# Lily.net
KiCad netlist of a schematic drawn in Altium Designer
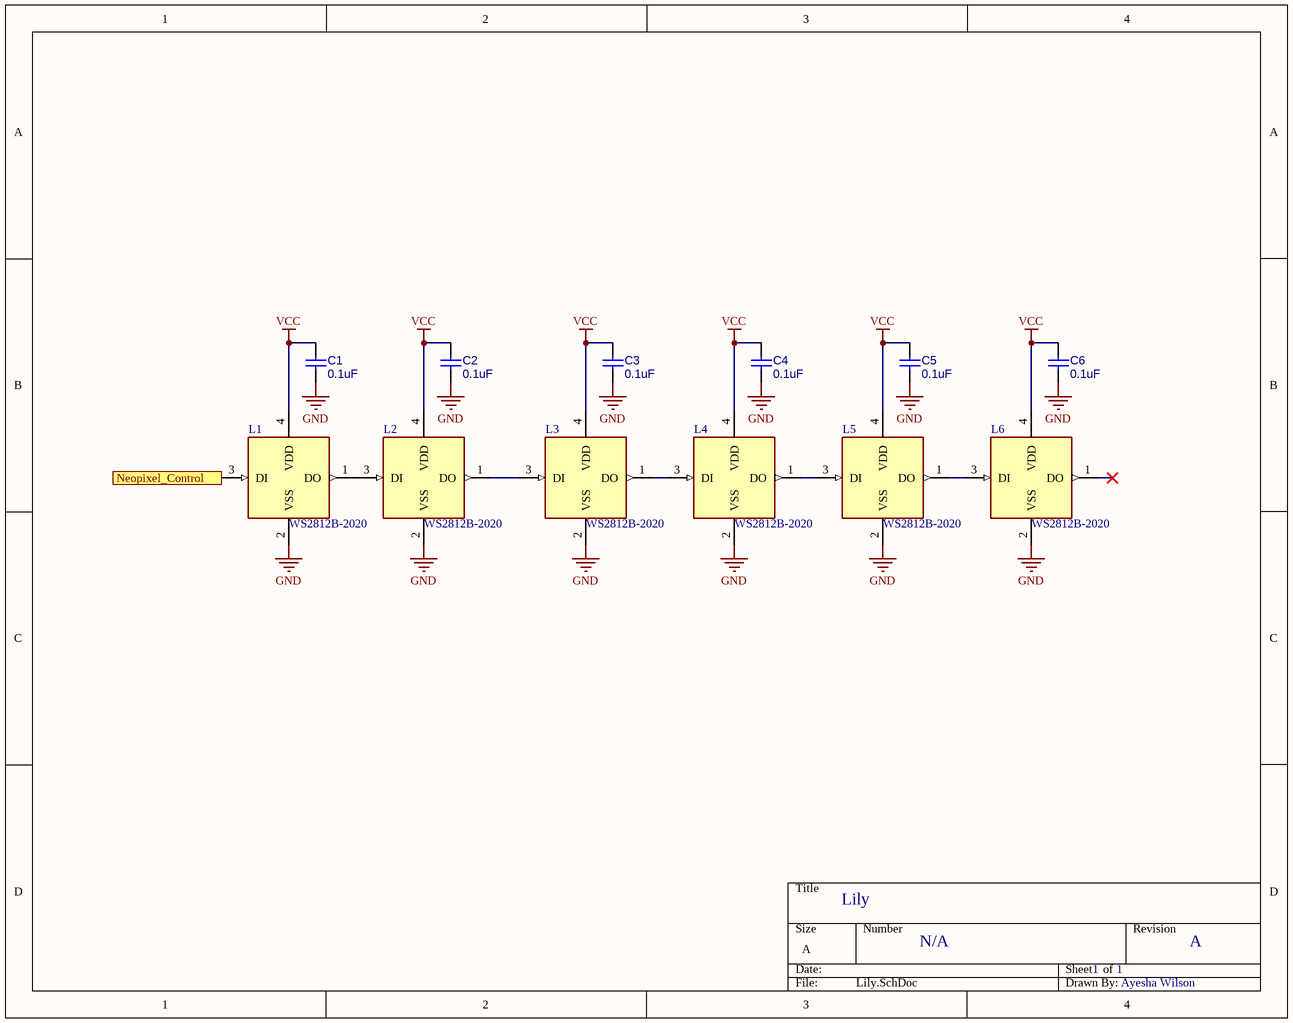
[diagram p0: Lily.SchDoc]

(export (version "E")
  (design (tool "Eeschema 10.0.6"))
  (components
    (comp (ref "C1")
      (value "0.1uF")
      (footprint "CC1005-0402")
      (description "CAP,CER,4.7UF,10%,25V,X5R,0805")
      (fields (field (name "Comment") "Cap-NP"))
      (libsource (lib "Schlib1") (part "Cap-NP"))
    )
    (comp (ref "C2")
      (value "0.1uF")
      (footprint "CC1005-0402")
      (description "CAP,CER,4.7UF,10%,25V,X5R,0805")
      (fields (field (name "Comment") "Cap-NP"))
      (libsource (lib "Schlib1") (part "Cap-NP"))
    )
    (comp (ref "C3")
      (value "0.1uF")
      (footprint "CC1005-0402")
      (description "CAP,CER,4.7UF,10%,25V,X5R,0805")
      (fields (field (name "Comment") "Cap-NP"))
      (libsource (lib "Schlib1") (part "Cap-NP"))
    )
    (comp (ref "C4")
      (value "0.1uF")
      (footprint "CC1005-0402")
      (description "CAP,CER,4.7UF,10%,25V,X5R,0805")
      (fields (field (name "Comment") "Cap-NP"))
      (libsource (lib "Schlib1") (part "Cap-NP"))
    )
    (comp (ref "C5")
      (value "0.1uF")
      (footprint "CC1005-0402")
      (description "CAP,CER,4.7UF,10%,25V,X5R,0805")
      (fields (field (name "Comment") "Cap-NP"))
      (libsource (lib "Schlib1") (part "Cap-NP"))
    )
    (comp (ref "C6")
      (value "0.1uF")
      (footprint "CC1005-0402")
      (description "CAP,CER,4.7UF,10%,25V,X5R,0805")
      (fields (field (name "Comment") "Cap-NP"))
      (libsource (lib "Schlib1") (part "Cap-NP"))
    )
    (comp (ref "L1")
      (value "WS2812B-2020")
      (footprint "WS2812B-2020")
      (description "LED; SMD; 2020; RGB; 2x2x0.84mm; 3.7Ã·5.3V; Lens: transparent; 2kHz")
      (fields (field (name "MF") "WorldSemi") (field (name "MP") "WS2812B2020"))
      (libsource (lib "Schlib1") (part "WS2812B-2020"))
    )
    (comp (ref "L2")
      (value "WS2812B-2020")
      (footprint "WS2812B-2020")
      (description "LED; SMD; 2020; RGB; 2x2x0.84mm; 3.7Ã·5.3V; Lens: transparent; 2kHz")
      (fields (field (name "MF") "WorldSemi") (field (name "MP") "WS2812B2020"))
      (libsource (lib "Schlib1") (part "WS2812B-2020"))
    )
    (comp (ref "L3")
      (value "WS2812B-2020")
      (footprint "WS2812B-2020")
      (description "LED; SMD; 2020; RGB; 2x2x0.84mm; 3.7Ã·5.3V; Lens: transparent; 2kHz")
      (fields (field (name "MF") "WorldSemi") (field (name "MP") "WS2812B2020"))
      (libsource (lib "Schlib1") (part "WS2812B-2020"))
    )
    (comp (ref "L4")
      (value "WS2812B-2020")
      (footprint "WS2812B-2020")
      (description "LED; SMD; 2020; RGB; 2x2x0.84mm; 3.7Ã·5.3V; Lens: transparent; 2kHz")
      (fields (field (name "MF") "WorldSemi") (field (name "MP") "WS2812B2020"))
      (libsource (lib "Schlib1") (part "WS2812B-2020"))
    )
    (comp (ref "L5")
      (value "WS2812B-2020")
      (footprint "WS2812B-2020")
      (description "LED; SMD; 2020; RGB; 2x2x0.84mm; 3.7Ã·5.3V; Lens: transparent; 2kHz")
      (fields (field (name "MF") "WorldSemi") (field (name "MP") "WS2812B2020"))
      (libsource (lib "Schlib1") (part "WS2812B-2020"))
    )
    (comp (ref "L6")
      (value "WS2812B-2020")
      (footprint "WS2812B-2020")
      (description "LED; SMD; 2020; RGB; 2x2x0.84mm; 3.7Ã·5.3V; Lens: transparent; 2kHz")
      (fields (field (name "MF") "WorldSemi") (field (name "MP") "WS2812B2020"))
      (libsource (lib "Schlib1") (part "WS2812B-2020"))
    )
  )
  (nets
    (net (code "1") (name "/Neopixel_Control") (class "Default")
      (node (ref "L1") (pin "3") (pinfunction "DI_3") (pintype "input"))
    )
    (net (code "2") (name "GND") (class "Default")
      (node (ref "C1") (pin "2") (pintype "passive"))
      (node (ref "C2") (pin "2") (pintype "passive"))
      (node (ref "C3") (pin "2") (pintype "passive"))
      (node (ref "C4") (pin "2") (pintype "passive"))
      (node (ref "C5") (pin "2") (pintype "passive"))
      (node (ref "C6") (pin "2") (pintype "passive"))
      (node (ref "L1") (pin "2") (pinfunction "VSS_2") (pintype "power_in"))
      (node (ref "L2") (pin "2") (pinfunction "VSS_2") (pintype "power_in"))
      (node (ref "L3") (pin "2") (pinfunction "VSS_2") (pintype "power_in"))
      (node (ref "L4") (pin "2") (pinfunction "VSS_2") (pintype "power_in"))
      (node (ref "L5") (pin "2") (pinfunction "VSS_2") (pintype "power_in"))
      (node (ref "L6") (pin "2") (pinfunction "VSS_2") (pintype "power_in"))
    )
    (net (code "3") (name "Net-(L1-DO)") (class "Default")
      (node (ref "L1") (pin "1") (pinfunction "DO_1") (pintype "output"))
      (node (ref "L2") (pin "3") (pinfunction "DI_3") (pintype "input"))
    )
    (net (code "4") (name "Net-(L2-DO)") (class "Default")
      (node (ref "L2") (pin "1") (pinfunction "DO_1") (pintype "output"))
      (node (ref "L3") (pin "3") (pinfunction "DI_3") (pintype "input"))
    )
    (net (code "5") (name "Net-(L3-DO)") (class "Default")
      (node (ref "L3") (pin "1") (pinfunction "DO_1") (pintype "output"))
      (node (ref "L4") (pin "3") (pinfunction "DI_3") (pintype "input"))
    )
    (net (code "6") (name "Net-(L4-DO)") (class "Default")
      (node (ref "L4") (pin "1") (pinfunction "DO_1") (pintype "output"))
      (node (ref "L5") (pin "3") (pinfunction "DI_3") (pintype "input"))
    )
    (net (code "7") (name "Net-(L5-DO)") (class "Default")
      (node (ref "L5") (pin "1") (pinfunction "DO_1") (pintype "output"))
      (node (ref "L6") (pin "3") (pinfunction "DI_3") (pintype "input"))
    )
    (net (code "8") (name "VCC") (class "Default")
      (node (ref "C1") (pin "1") (pintype "passive"))
      (node (ref "C2") (pin "1") (pintype "passive"))
      (node (ref "C3") (pin "1") (pintype "passive"))
      (node (ref "C4") (pin "1") (pintype "passive"))
      (node (ref "C5") (pin "1") (pintype "passive"))
      (node (ref "C6") (pin "1") (pintype "passive"))
      (node (ref "L1") (pin "4") (pinfunction "VDD_4") (pintype "power_in"))
      (node (ref "L2") (pin "4") (pinfunction "VDD_4") (pintype "power_in"))
      (node (ref "L3") (pin "4") (pinfunction "VDD_4") (pintype "power_in"))
      (node (ref "L4") (pin "4") (pinfunction "VDD_4") (pintype "power_in"))
      (node (ref "L5") (pin "4") (pinfunction "VDD_4") (pintype "power_in"))
      (node (ref "L6") (pin "4") (pinfunction "VDD_4") (pintype "power_in"))
    )
    (net (code "9") (name "unconnected-(L6-DO-Pad1)") (class "Default")
      (node (ref "L6") (pin "1") (pinfunction "DO_1") (pintype "output+no_connect"))
    )
  )
)
